# SCH_DART-Flight-Computer-4_2024-07-14.net
KiCad netlist of a schematic drawn in EasyEDA
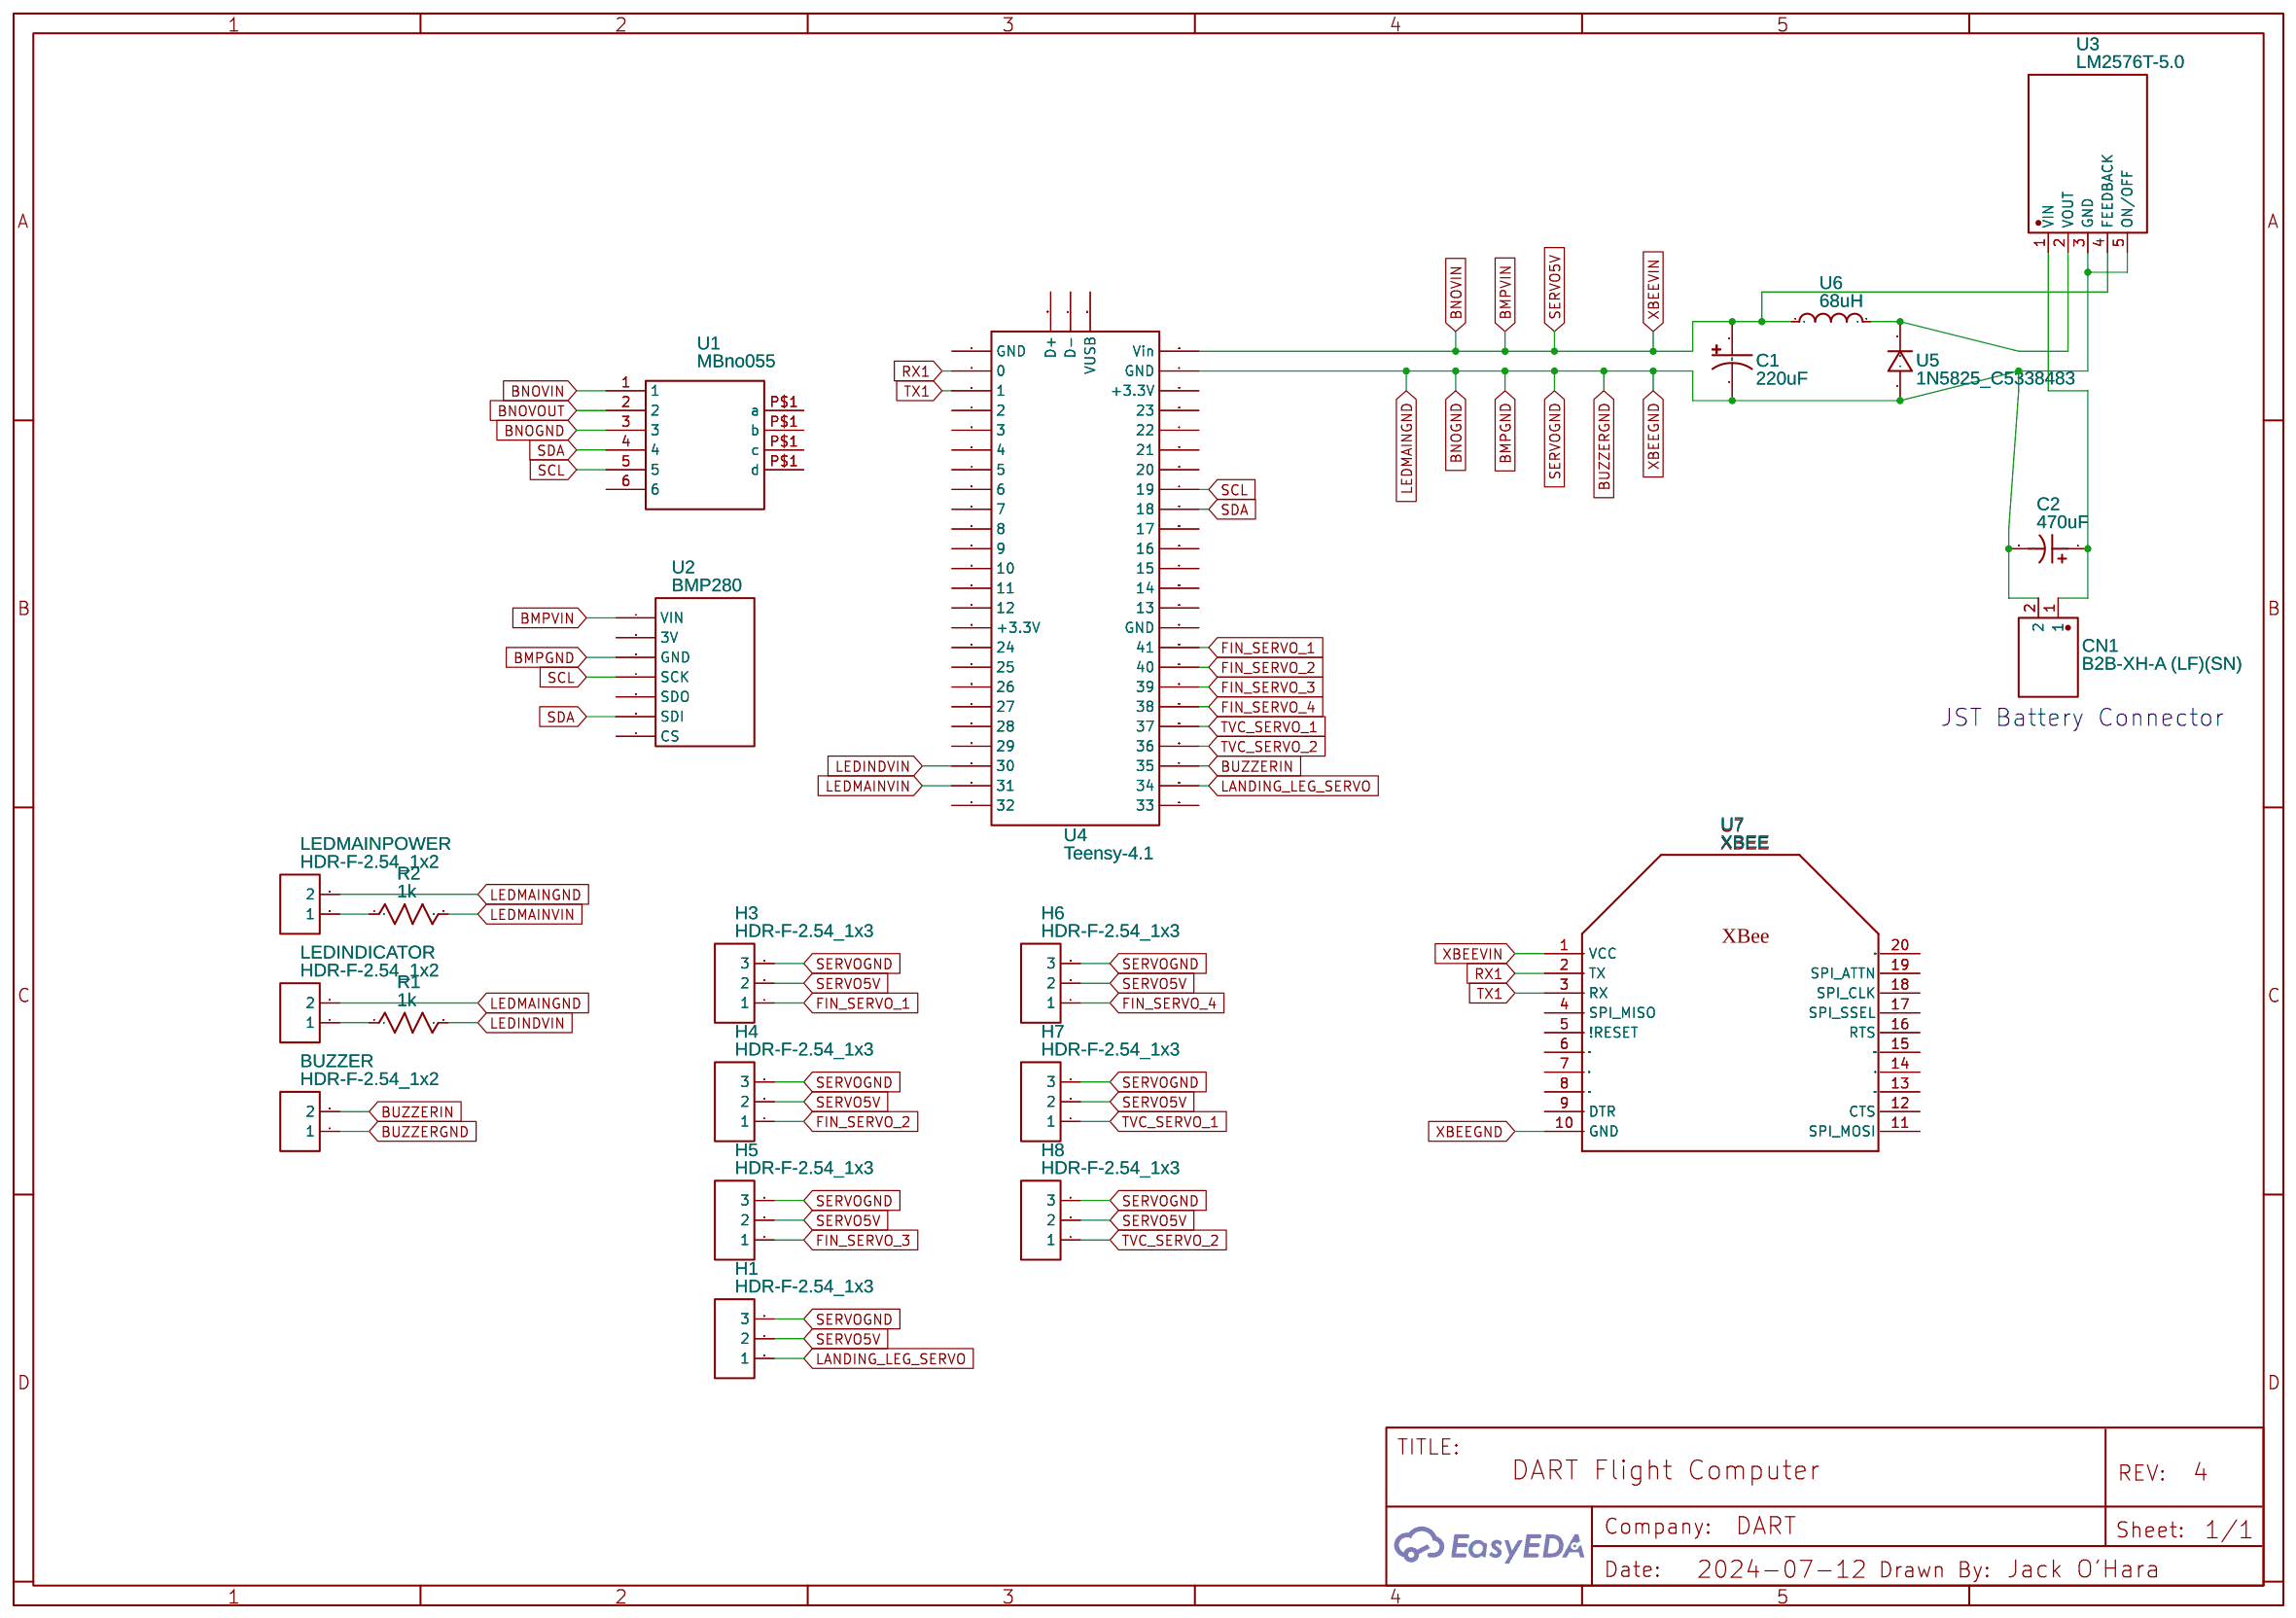
[diagram p0: schematic sheet]

(export (version "E")
  (design (tool "Eeschema 10.0.6"))
  (components
    (comp (ref "BUZZER") (value "HDR-F-2.54_1x2") (libsource (lib "") (part "HDR-F-2.54_1x2_2")))
    (comp (ref "C1")
      (value "220uF")
      (fields (field (name "Manufacturer Part") "UPW1E221MPD") (field (name "Manufacturer") "Nichicon(尼吉康)"))
      (libsource (lib "") (part "UPW1E221MPD"))
    )
    (comp (ref "C2")
      (value "470uF")
      (fields (field (name "Manufacturer Part") "152EC0399") (field (name "Manufacturer") "KNSCHA(科尼盛)"))
      (libsource (lib "") (part "152EC0399"))
    )
    (comp (ref "CN1")
      (value "B2B-XH-A (LF)(SN)")
      (fields (field (name "Manufacturer Part") "B2B-XH-A(LF)(SN)") (field (name "Manufacturer") "JST"))
      (libsource (lib "") (part "B2B-XH-A (LF)(SN)"))
    )
    (comp (ref "H1") (value "HDR-F-2.54_1x3") (libsource (lib "") (part "HDR-F-2.54_1x3")))
    (comp (ref "H3") (value "HDR-F-2.54_1x3") (libsource (lib "") (part "HDR-F-2.54_1x3")))
    (comp (ref "H4") (value "HDR-F-2.54_1x3") (libsource (lib "") (part "HDR-F-2.54_1x3")))
    (comp (ref "H5") (value "HDR-F-2.54_1x3") (libsource (lib "") (part "HDR-F-2.54_1x3")))
    (comp (ref "H6") (value "HDR-F-2.54_1x3") (libsource (lib "") (part "HDR-F-2.54_1x3")))
    (comp (ref "H7") (value "HDR-F-2.54_1x3") (libsource (lib "") (part "HDR-F-2.54_1x3")))
    (comp (ref "H8") (value "HDR-F-2.54_1x3") (libsource (lib "") (part "HDR-F-2.54_1x3")))
    (comp (ref "LEDINDICATOR") (value "HDR-F-2.54_1x2") (libsource (lib "") (part "HDR-F-2.54_1x2_1")))
    (comp (ref "LEDMAINPOWER") (value "HDR-F-2.54_1x2") (libsource (lib "") (part "HDR-F-2.54_1x2")))
    (comp (ref "R1") (value "1k") (libsource (lib "") (part "R_0603_US")))
    (comp (ref "R2") (value "1k") (libsource (lib "") (part "R_0603_US")))
    (comp (ref "U1") (value "MBno055") (libsource (lib "") (part "MBno055")))
    (comp (ref "U2") (value "BMP280") (libsource (lib "") (part "BMP280")))
    (comp (ref "U3")
      (value "LM2576T-5.0")
      (fields (field (name "Manufacturer") "HTC"))
      (libsource (lib "") (part "LM2576T-5.0"))
    )
    (comp (ref "U4") (value "Teensy-4.1") (libsource (lib "") (part "Teensy-4.1")))
    (comp (ref "U5")
      (value "1N5825_C5338483")
      (fields (field (name "Manufacturer Part") "1N5825") (field (name "Manufacturer") "SUNMATE(森美特)"))
      (libsource (lib "") (part "1N5825_C5338483"))
    )
    (comp (ref "U6")
      (value "68uH")
      (fields (field (name "Manufacturer Part") "SRR1210-680M") (field (name "Manufacturer") "BOURNS"))
      (libsource (lib "") (part "SRR1210-680M"))
    )
    (comp (ref "U7") (value "XBEE") (libsource (lib "") (part "XBEE")))
  )
  (nets
    (net (code "1") (name "BMPGND") (class "Default")
      (node (ref "BUZZER") (pin "1") (pinfunction "1_1") (pintype "input"))
      (node (ref "C1") (pin "2") (pinfunction "2_2") (pintype "unspecified"))
      (node (ref "C2") (pin "2") (pinfunction "2_2") (pintype "input"))
      (node (ref "CN1") (pin "2") (pinfunction "2_2") (pintype "unspecified"))
      (node (ref "H1") (pin "3") (pinfunction "3_3") (pintype "input"))
      (node (ref "H3") (pin "3") (pinfunction "3_3") (pintype "input"))
      (node (ref "H4") (pin "3") (pinfunction "3_3") (pintype "input"))
      (node (ref "H5") (pin "3") (pinfunction "3_3") (pintype "input"))
      (node (ref "H6") (pin "3") (pinfunction "3_3") (pintype "input"))
      (node (ref "H7") (pin "3") (pinfunction "3_3") (pintype "input"))
      (node (ref "H8") (pin "3") (pinfunction "3_3") (pintype "input"))
      (node (ref "LEDINDICATOR") (pin "2") (pinfunction "2_2") (pintype "input"))
      (node (ref "LEDMAINPOWER") (pin "2") (pinfunction "2_2") (pintype "input"))
      (node (ref "U1") (pin "3") (pinfunction "3_3") (pintype "unspecified"))
      (node (ref "U2") (pin "5") (pinfunction "GND_5") (pintype "unspecified"))
      (node (ref "U3") (pin "3") (pinfunction "GND_3") (pintype "unspecified"))
      (node (ref "U3") (pin "5") (pinfunction "ON/OFF_5") (pintype "unspecified"))
      (node (ref "U4") (pin "47") (pinfunction "GND_47") (pintype "unspecified"))
      (node (ref "U5") (pin "2") (pinfunction "A_2") (pintype "unspecified"))
      (node (ref "U7") (pin "10") (pinfunction "GND_10") (pintype "unspecified"))
    )
    (net (code "2") (name "BMPVIN") (class "Default")
      (node (ref "C1") (pin "1") (pinfunction "1_1") (pintype "unspecified"))
      (node (ref "H1") (pin "2") (pinfunction "2_2") (pintype "input"))
      (node (ref "H3") (pin "2") (pinfunction "2_2") (pintype "input"))
      (node (ref "H4") (pin "2") (pinfunction "2_2") (pintype "input"))
      (node (ref "H5") (pin "2") (pinfunction "2_2") (pintype "input"))
      (node (ref "H6") (pin "2") (pinfunction "2_2") (pintype "input"))
      (node (ref "H7") (pin "2") (pinfunction "2_2") (pintype "input"))
      (node (ref "H8") (pin "2") (pinfunction "2_2") (pintype "input"))
      (node (ref "U1") (pin "1") (pinfunction "1_1") (pintype "unspecified"))
      (node (ref "U2") (pin "7") (pinfunction "VIN_7") (pintype "unspecified"))
      (node (ref "U3") (pin "4") (pinfunction "FEEDBACK_4") (pintype "unspecified"))
      (node (ref "U4") (pin "48") (pinfunction "Vin_48") (pintype "unspecified"))
      (node (ref "U6") (pin "1") (pinfunction "1_1") (pintype "unspecified"))
      (node (ref "U7") (pin "1") (pinfunction "VCC_1") (pintype "unspecified"))
    )
    (net (code "3") (name "BNOVOUT") (class "Default")
      (node (ref "U1") (pin "2") (pinfunction "2_2") (pintype "unspecified"))
    )
    (net (code "4") (name "BUZZERIN") (class "Default")
      (node (ref "BUZZER") (pin "2") (pinfunction "2_2") (pintype "input"))
      (node (ref "U4") (pin "27") (pinfunction "35_27") (pintype "unspecified"))
    )
    (net (code "5") (name "FIN_SERVO_1") (class "Default")
      (node (ref "H3") (pin "1") (pinfunction "1_1") (pintype "input"))
      (node (ref "U4") (pin "33") (pinfunction "41_33") (pintype "unspecified"))
    )
    (net (code "6") (name "FIN_SERVO_2") (class "Default")
      (node (ref "H4") (pin "1") (pinfunction "1_1") (pintype "input"))
      (node (ref "U4") (pin "32") (pinfunction "40_32") (pintype "unspecified"))
    )
    (net (code "7") (name "FIN_SERVO_3") (class "Default")
      (node (ref "H5") (pin "1") (pinfunction "1_1") (pintype "input"))
      (node (ref "U4") (pin "31") (pinfunction "39_31") (pintype "unspecified"))
    )
    (net (code "8") (name "FIN_SERVO_4") (class "Default")
      (node (ref "H6") (pin "1") (pinfunction "1_1") (pintype "input"))
      (node (ref "U4") (pin "30") (pinfunction "38_30") (pintype "unspecified"))
    )
    (net (code "9") (name "LANDING_LEG_SERVO") (class "Default")
      (node (ref "H1") (pin "1") (pinfunction "1_1") (pintype "input"))
      (node (ref "U4") (pin "26") (pinfunction "34_26") (pintype "unspecified"))
    )
    (net (code "10") (name "LEDINDVIN") (class "Default")
      (node (ref "R1") (pin "2") (pinfunction "2_2") (pintype "unspecified"))
      (node (ref "U4") (pin "22") (pinfunction "30_22") (pintype "unspecified"))
    )
    (net (code "11") (name "LEDMAINVIN") (class "Default")
      (node (ref "R2") (pin "2") (pinfunction "2_2") (pintype "unspecified"))
      (node (ref "U4") (pin "23") (pinfunction "31_23") (pintype "unspecified"))
    )
    (net (code "12") (name "Net-(LEDINDICATOR-Pad1)") (class "Default")
      (node (ref "LEDINDICATOR") (pin "1") (pinfunction "1_1") (pintype "input"))
      (node (ref "R1") (pin "1") (pinfunction "1_1") (pintype "unspecified"))
    )
    (net (code "13") (name "Net-(LEDMAINPOWER-Pad1)") (class "Default")
      (node (ref "LEDMAINPOWER") (pin "1") (pinfunction "1_1") (pintype "input"))
      (node (ref "R2") (pin "1") (pinfunction "1_1") (pintype "unspecified"))
    )
    (net (code "14") (name "Net-(U3-VIN)") (class "Default")
      (node (ref "C2") (pin "1") (pinfunction "1_1") (pintype "input"))
      (node (ref "CN1") (pin "1") (pinfunction "1_1") (pintype "unspecified"))
      (node (ref "U3") (pin "1") (pinfunction "VIN_1") (pintype "unspecified"))
    )
    (net (code "15") (name "Net-(U3-VOUT)") (class "Default")
      (node (ref "U3") (pin "2") (pinfunction "VOUT_2") (pintype "unspecified"))
      (node (ref "U5") (pin "1") (pinfunction "C_1") (pintype "unspecified"))
      (node (ref "U6") (pin "2") (pinfunction "2_2") (pintype "unspecified"))
    )
    (net (code "16") (name "RX1") (class "Default")
      (node (ref "U4") (pin "2") (pinfunction "0_2") (pintype "unspecified"))
      (node (ref "U7") (pin "2") (pinfunction "TX_2") (pintype "output"))
    )
    (net (code "17") (name "SCL") (class "Default")
      (node (ref "U1") (pin "5") (pinfunction "5_5") (pintype "unspecified"))
      (node (ref "U2") (pin "4") (pinfunction "SCK_4") (pintype "unspecified"))
      (node (ref "U4") (pin "41") (pinfunction "19_41") (pintype "unspecified"))
    )
    (net (code "18") (name "SDA") (class "Default")
      (node (ref "U1") (pin "4") (pinfunction "4_4") (pintype "unspecified"))
      (node (ref "U2") (pin "2") (pinfunction "SDI_2") (pintype "unspecified"))
      (node (ref "U4") (pin "40") (pinfunction "18_40") (pintype "unspecified"))
    )
    (net (code "19") (name "TVC_SERVO_1") (class "Default")
      (node (ref "H7") (pin "1") (pinfunction "1_1") (pintype "input"))
      (node (ref "U4") (pin "29") (pinfunction "37_29") (pintype "unspecified"))
    )
    (net (code "20") (name "TVC_SERVO_2") (class "Default")
      (node (ref "H8") (pin "1") (pinfunction "1_1") (pintype "input"))
      (node (ref "U4") (pin "28") (pinfunction "36_28") (pintype "unspecified"))
    )
    (net (code "21") (name "TX1") (class "Default")
      (node (ref "U4") (pin "3") (pinfunction "1_3") (pintype "unspecified"))
      (node (ref "U7") (pin "3") (pinfunction "RX_3") (pintype "input"))
    )
    (net (code "22") (name "unconnected-(U1-Pad6)") (class "Default")
      (node (ref "U1") (pin "6") (pinfunction "6_6") (pintype "unspecified"))
    )
    (net (code "23") (name "unconnected-(U1-a-PadP$1)") (class "Default")
      (node (ref "U1") (pin "P$1") (pinfunction "a_P$1") (pintype "unspecified"))
    )
    (net (code "24") (name "unconnected-(U1-b-PadP$1)") (class "Default")
      (node (ref "U1") (pin "P$1") (pinfunction "b_P$1") (pintype "unspecified"))
    )
    (net (code "25") (name "unconnected-(U1-c-PadP$1)") (class "Default")
      (node (ref "U1") (pin "P$1") (pinfunction "c_P$1") (pintype "unspecified"))
    )
    (net (code "26") (name "unconnected-(U1-d-PadP$1)") (class "Default")
      (node (ref "U1") (pin "P$1") (pinfunction "d_P$1") (pintype "unspecified"))
    )
    (net (code "27") (name "unconnected-(U2-3V-Pad6)") (class "Default")
      (node (ref "U2") (pin "6") (pinfunction "3V_6") (pintype "unspecified"))
    )
    (net (code "28") (name "unconnected-(U2-CS-Pad1)") (class "Default")
      (node (ref "U2") (pin "1") (pinfunction "CS_1") (pintype "unspecified"))
    )
    (net (code "29") (name "unconnected-(U2-SDO-Pad3)") (class "Default")
      (node (ref "U2") (pin "3") (pinfunction "SDO_3") (pintype "unspecified"))
    )
    (net (code "30") (name "unconnected-(U4-+3.3V-Pad15)") (class "Default")
      (node (ref "U4") (pin "15") (pinfunction "+3.3V_15") (pintype "unspecified"))
    )
    (net (code "31") (name "unconnected-(U4-+3.3V-Pad46)") (class "Default")
      (node (ref "U4") (pin "46") (pinfunction "+3.3V_46") (pintype "unspecified"))
    )
    (net (code "32") (name "unconnected-(U4-2-Pad4)") (class "Default")
      (node (ref "U4") (pin "4") (pinfunction "2_4") (pintype "unspecified"))
    )
    (net (code "33") (name "unconnected-(U4-3-Pad5)") (class "Default")
      (node (ref "U4") (pin "5") (pinfunction "3_5") (pintype "unspecified"))
    )
    (net (code "34") (name "unconnected-(U4-4-Pad6)") (class "Default")
      (node (ref "U4") (pin "6") (pinfunction "4_6") (pintype "unspecified"))
    )
    (net (code "35") (name "unconnected-(U4-5-Pad7)") (class "Default")
      (node (ref "U4") (pin "7") (pinfunction "5_7") (pintype "unspecified"))
    )
    (net (code "36") (name "unconnected-(U4-6-Pad8)") (class "Default")
      (node (ref "U4") (pin "8") (pinfunction "6_8") (pintype "unspecified"))
    )
    (net (code "37") (name "unconnected-(U4-7-Pad9)") (class "Default")
      (node (ref "U4") (pin "9") (pinfunction "7_9") (pintype "unspecified"))
    )
    (net (code "38") (name "unconnected-(U4-8-Pad10)") (class "Default")
      (node (ref "U4") (pin "10") (pinfunction "8_10") (pintype "unspecified"))
    )
    (net (code "39") (name "unconnected-(U4-9-Pad11)") (class "Default")
      (node (ref "U4") (pin "11") (pinfunction "9_11") (pintype "unspecified"))
    )
    (net (code "40") (name "unconnected-(U4-10-Pad12)") (class "Default")
      (node (ref "U4") (pin "12") (pinfunction "10_12") (pintype "unspecified"))
    )
    (net (code "41") (name "unconnected-(U4-11-Pad13)") (class "Default")
      (node (ref "U4") (pin "13") (pinfunction "11_13") (pintype "unspecified"))
    )
    (net (code "42") (name "unconnected-(U4-12-Pad14)") (class "Default")
      (node (ref "U4") (pin "14") (pinfunction "12_14") (pintype "unspecified"))
    )
    (net (code "43") (name "unconnected-(U4-13-Pad35)") (class "Default")
      (node (ref "U4") (pin "35") (pinfunction "13_35") (pintype "unspecified"))
    )
    (net (code "44") (name "unconnected-(U4-14-Pad36)") (class "Default")
      (node (ref "U4") (pin "36") (pinfunction "14_36") (pintype "unspecified"))
    )
    (net (code "45") (name "unconnected-(U4-15-Pad37)") (class "Default")
      (node (ref "U4") (pin "37") (pinfunction "15_37") (pintype "unspecified"))
    )
    (net (code "46") (name "unconnected-(U4-16-Pad38)") (class "Default")
      (node (ref "U4") (pin "38") (pinfunction "16_38") (pintype "unspecified"))
    )
    (net (code "47") (name "unconnected-(U4-17-Pad39)") (class "Default")
      (node (ref "U4") (pin "39") (pinfunction "17_39") (pintype "unspecified"))
    )
    (net (code "48") (name "unconnected-(U4-20-Pad42)") (class "Default")
      (node (ref "U4") (pin "42") (pinfunction "20_42") (pintype "unspecified"))
    )
    (net (code "49") (name "unconnected-(U4-21-Pad43)") (class "Default")
      (node (ref "U4") (pin "43") (pinfunction "21_43") (pintype "unspecified"))
    )
    (net (code "50") (name "unconnected-(U4-22-Pad44)") (class "Default")
      (node (ref "U4") (pin "44") (pinfunction "22_44") (pintype "unspecified"))
    )
    (net (code "51") (name "unconnected-(U4-23-Pad45)") (class "Default")
      (node (ref "U4") (pin "45") (pinfunction "23_45") (pintype "unspecified"))
    )
    (net (code "52") (name "unconnected-(U4-24-Pad16)") (class "Default")
      (node (ref "U4") (pin "16") (pinfunction "24_16") (pintype "unspecified"))
    )
    (net (code "53") (name "unconnected-(U4-25-Pad17)") (class "Default")
      (node (ref "U4") (pin "17") (pinfunction "25_17") (pintype "unspecified"))
    )
    (net (code "54") (name "unconnected-(U4-26-Pad18)") (class "Default")
      (node (ref "U4") (pin "18") (pinfunction "26_18") (pintype "unspecified"))
    )
    (net (code "55") (name "unconnected-(U4-27-Pad19)") (class "Default")
      (node (ref "U4") (pin "19") (pinfunction "27_19") (pintype "unspecified"))
    )
    (net (code "56") (name "unconnected-(U4-28-Pad20)") (class "Default")
      (node (ref "U4") (pin "20") (pinfunction "28_20") (pintype "unspecified"))
    )
    (net (code "57") (name "unconnected-(U4-29-Pad21)") (class "Default")
      (node (ref "U4") (pin "21") (pinfunction "29_21") (pintype "unspecified"))
    )
    (net (code "58") (name "unconnected-(U4-32-Pad24)") (class "Default")
      (node (ref "U4") (pin "24") (pinfunction "32_24") (pintype "unspecified"))
    )
    (net (code "59") (name "unconnected-(U4-33-Pad25)") (class "Default")
      (node (ref "U4") (pin "25") (pinfunction "33_25") (pintype "unspecified"))
    )
    (net (code "60") (name "unconnected-(U4-D+-Pad66)") (class "Default")
      (node (ref "U4") (pin "66") (pinfunction "D+_66") (pintype "unspecified"))
    )
    (net (code "61") (name "unconnected-(U4-D--Pad67)") (class "Default")
      (node (ref "U4") (pin "67") (pinfunction "D-_67") (pintype "unspecified"))
    )
    (net (code "62") (name "unconnected-(U4-GND-Pad1)") (class "Default")
      (node (ref "U4") (pin "1") (pinfunction "GND_1") (pintype "unspecified"))
    )
    (net (code "63") (name "unconnected-(U4-GND-Pad34)") (class "Default")
      (node (ref "U4") (pin "34") (pinfunction "GND_34") (pintype "unspecified"))
    )
    (net (code "64") (name "unconnected-(U4-VUSB-Pad52)") (class "Default")
      (node (ref "U4") (pin "52") (pinfunction "VUSB_52") (pintype "unspecified"))
    )
    (net (code "65") (name "unconnected-(U7-!RESET-Pad5)") (class "Default")
      (node (ref "U7") (pin "5") (pinfunction "!RESET_5") (pintype "input"))
    )
    (net (code "66") (name "unconnected-(U7-AD0DIO0-Pad20)") (class "Default")
      (node (ref "U7") (pin "20") (pinfunction "AD0DIO0_20") (pintype "unspecified"))
    )
    (net (code "67") (name "unconnected-(U7-ASCAD5DIO5-Pad15)") (class "Default")
      (node (ref "U7") (pin "15") (pinfunction "ASCAD5DIO5_15") (pintype "unspecified"))
    )
    (net (code "68") (name "unconnected-(U7-CTS-Pad12)") (class "Default")
      (node (ref "U7") (pin "12") (pinfunction "CTS_12") (pintype "unspecified"))
    )
    (net (code "69") (name "unconnected-(U7-DTR-Pad9)") (class "Default")
      (node (ref "U7") (pin "9") (pinfunction "DTR_9") (pintype "unspecified"))
    )
    (net (code "70") (name "unconnected-(U7-ONSLEEP-Pad13)") (class "Default")
      (node (ref "U7") (pin "13") (pinfunction "ONSLEEP_13") (pintype "output"))
    )
    (net (code "71") (name "unconnected-(U7-PWM0RSSI-Pad6)") (class "Default")
      (node (ref "U7") (pin "6") (pinfunction "PWM0RSSI_6") (pintype "output"))
    )
    (net (code "72") (name "unconnected-(U7-PWM1-Pad7)") (class "Default")
      (node (ref "U7") (pin "7") (pinfunction "PWM1_7") (pintype "output"))
    )
    (net (code "73") (name "unconnected-(U7-RESERVED-Pad8)") (class "Default")
      (node (ref "U7") (pin "8") (pinfunction "RESERVED_8") (pintype "unspecified"))
    )
    (net (code "74") (name "unconnected-(U7-RTS-Pad16)") (class "Default")
      (node (ref "U7") (pin "16") (pinfunction "RTS_16") (pintype "unspecified"))
    )
    (net (code "75") (name "unconnected-(U7-SPI_ATTN-Pad19)") (class "Default")
      (node (ref "U7") (pin "19") (pinfunction "SPI_ATTN_19") (pintype "unspecified"))
    )
    (net (code "76") (name "unconnected-(U7-SPI_CLK-Pad18)") (class "Default")
      (node (ref "U7") (pin "18") (pinfunction "SPI_CLK_18") (pintype "unspecified"))
    )
    (net (code "77") (name "unconnected-(U7-SPI_MISO-Pad4)") (class "Default")
      (node (ref "U7") (pin "4") (pinfunction "SPI_MISO_4") (pintype "output"))
    )
    (net (code "78") (name "unconnected-(U7-SPI_MOSI-Pad11)") (class "Default")
      (node (ref "U7") (pin "11") (pinfunction "SPI_MOSI_11") (pintype "unspecified"))
    )
    (net (code "79") (name "unconnected-(U7-SPI_SSEL-Pad17)") (class "Default")
      (node (ref "U7") (pin "17") (pinfunction "SPI_SSEL_17") (pintype "unspecified"))
    )
    (net (code "80") (name "unconnected-(U7-VREF-Pad14)") (class "Default")
      (node (ref "U7") (pin "14") (pinfunction "VREF_14") (pintype "input"))
    )
  )
)
